# attiny85.net
KiCad netlist of a schematic drawn in EAGLE
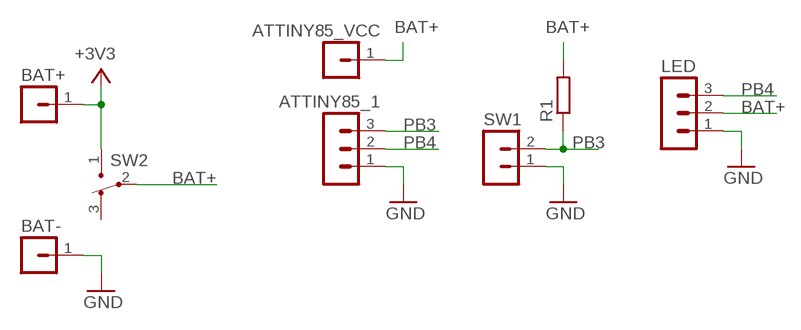
[diagram p0: schematic, sheet 1]

(export (version "E")
  (design (tool "Eeschema 10.0.6"))
  (components
    (comp (ref "ATTINY85_1")
      (value "PINHEAD-MA03-1")
      (footprint "eagle-import:PINHEAD-MA03-1")
      (libsource (lib "eagle-import") (part "PINHEAD-MA03-1"))
    )
    (comp (ref "ATTINY85_VCC")
      (value "PINHEAD-MA01-1")
      (footprint "eagle-import:PINHEAD-MA01-1")
      (libsource (lib "eagle-import") (part "PINHEAD-MA01-1"))
    )
    (comp (ref "BAT+")
      (value "PINHEAD-MA01-1")
      (footprint "eagle-import:PINHEAD-MA01-1")
      (libsource (lib "eagle-import") (part "PINHEAD-MA01-1"))
    )
    (comp (ref "BAT-")
      (value "PINHEAD-MA01-1")
      (footprint "eagle-import:PINHEAD-MA01-1")
      (libsource (lib "eagle-import") (part "PINHEAD-MA01-1"))
    )
    (comp (ref "LED")
      (value "PINHEAD-MA03-1")
      (footprint "eagle-import:PINHEAD-MA03-1")
      (libsource (lib "eagle-import") (part "PINHEAD-MA03-1"))
    )
    (comp (ref "R1")
      (value "R-EU_0204/5")
      (footprint "eagle-import:0204_5")
      (libsource (lib "eagle-import") (part "R-EU_0204/5"))
    )
    (comp (ref "SW1")
      (value "PINHEAD-MA02-1")
      (footprint "eagle-import:PINHEAD-MA02-1")
      (libsource (lib "eagle-import") (part "PINHEAD-MA02-1"))
    )
    (comp (ref "SW2")
      (value "SW3-1")
      (footprint "eagle-import:SW3-1")
      (fields (field (name "MF") "HiLetgo"))
      (libsource (lib "eagle-import") (part "SW3-1"))
    )
  )
  (nets
    (net (code "1") (name "+3V3") (class "Default")
      (node (ref "BAT+") (pin "1") (pinfunction "1_1") (pintype "passive"))
      (node (ref "SW2") (pin "1") (pinfunction "1_1") (pintype "passive"))
    )
    (net (code "2") (name "/BAT+") (class "Default")
      (node (ref "ATTINY85_VCC") (pin "1") (pinfunction "1_1") (pintype "passive"))
      (node (ref "LED") (pin "2") (pinfunction "2_2") (pintype "passive"))
      (node (ref "R1") (pin "2") (pinfunction "2_2") (pintype "passive"))
      (node (ref "SW2") (pin "2") (pinfunction "2_2") (pintype "passive"))
    )
    (net (code "3") (name "/PB3") (class "Default")
      (node (ref "ATTINY85_1") (pin "3") (pinfunction "3_3") (pintype "passive"))
      (node (ref "R1") (pin "1") (pinfunction "1_1") (pintype "passive"))
      (node (ref "SW1") (pin "2") (pinfunction "2_2") (pintype "passive"))
    )
    (net (code "4") (name "/PB4") (class "Default")
      (node (ref "ATTINY85_1") (pin "2") (pinfunction "2_2") (pintype "passive"))
      (node (ref "LED") (pin "3") (pinfunction "3_3") (pintype "passive"))
    )
    (net (code "5") (name "GND") (class "Default")
      (node (ref "ATTINY85_1") (pin "1") (pinfunction "1_1") (pintype "passive"))
      (node (ref "BAT-") (pin "1") (pinfunction "1_1") (pintype "passive"))
      (node (ref "LED") (pin "1") (pinfunction "1_1") (pintype "passive"))
      (node (ref "SW1") (pin "1") (pinfunction "1_1") (pintype "passive"))
    )
    (net (code "6") (name "unconnected-(SW2-Pad3)") (class "Default")
      (node (ref "SW2") (pin "3") (pinfunction "3_3") (pintype "passive"))
    )
  )
)
